# RF_Switch.net
KiCad netlist of a schematic drawn in Altium Designer
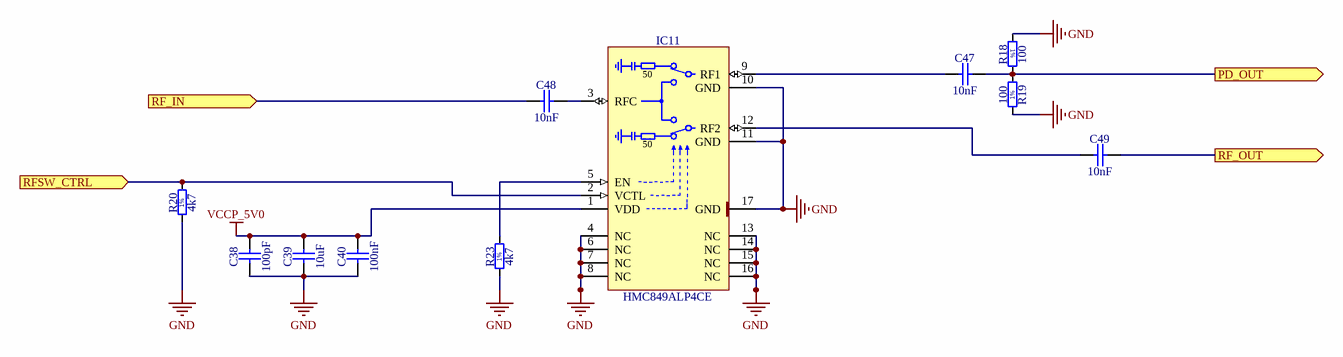
[diagram p0: RF_Switch.SchDoc]

(export (version "E")
  (design (tool "Eeschema 10.0.6"))
  (components
    (comp (ref "C38")
      (value "100pF")
      (footprint "CAPC1005X55N")
      (description "Non-polarised capacitor")
      (fields
        (field (name "PART NUMBER") "CC0402_100PF_50V_5%_C0G")
        (field (name "VOLTAGE") "50V")
        (field (name "AUTHOR") "CERN DEM JLC")
      )
      (libsource (lib "Capacitors") (part "Capacitor - non polarized"))
    )
    (comp (ref "C39")
      (value "10uF")
      (footprint "CAPC1608X80N")
      (description "Non-polarised capacitor")
      (fields
        (field (name "PART NUMBER") "CC0603_10UF_16V_20%_X5R")
        (field (name "VOLTAGE") "16V")
        (field (name "AUTHOR") "CERN DEM MR")
      )
      (libsource (lib "Capacitors") (part "Capacitor - non polarized"))
    )
    (comp (ref "C40")
      (value "100nF")
      (footprint "CAPC1005X55N")
      (description "Non-polarised capacitor")
      (fields
        (field (name "PART NUMBER") "CC0402_100NF_16V_10%_X7R")
        (field (name "VOLTAGE") "16V")
        (field (name "AUTHOR") "CERN DEM JLC")
      )
      (libsource (lib "Capacitors") (part "Capacitor - non polarized"))
    )
    (comp (ref "C47")
      (value "10nF")
      (footprint "CAPC1005X55N")
      (description "Non-polarised capacitor")
      (fields
        (field (name "PART NUMBER") "CC0402_10NF_16V_10%_X7R")
        (field (name "VOLTAGE") "16V")
        (field (name "AUTHOR") "CERN DEM JLC")
      )
      (libsource (lib "Capacitors") (part "Capacitor - non polarized"))
    )
    (comp (ref "C48")
      (value "10nF")
      (footprint "CAPC1005X55N")
      (description "Non-polarised capacitor")
      (fields
        (field (name "PART NUMBER") "CC0402_10NF_16V_10%_X7R")
        (field (name "VOLTAGE") "16V")
        (field (name "AUTHOR") "CERN DEM JLC")
      )
      (libsource (lib "Capacitors") (part "Capacitor - non polarized"))
    )
    (comp (ref "C49")
      (value "10nF")
      (footprint "CAPC1005X55N")
      (description "Non-polarised capacitor")
      (fields
        (field (name "PART NUMBER") "CC0402_10NF_16V_10%_X7R")
        (field (name "VOLTAGE") "16V")
        (field (name "AUTHOR") "CERN DEM JLC")
      )
      (libsource (lib "Capacitors") (part "Capacitor - non polarized"))
    )
    (comp (ref "IC11")
      (value "HMC849ALP4CE")
      (footprint "QFN65P400X400X100-17N-S255")
      (description "High Isolation SPDT Non-Reflective Switch SMT, DC - 6 GHz")
      (fields (field (name "MANUFACTURER") "ANALOG DEVICES") (field (name "AUTHOR") "CERN DEM MR"))
      (libsource (lib "ICs And Semiconductors") (part "HMC849ALP4CE"))
    )
    (comp (ref "R18")
      (value "100")
      (footprint "RESC0603X28N")
      (description "Resistor - 1%")
      (fields
        (field (name "PART NUMBER") "R0201_100R_1%_0.05W_200PPM")
        (field (name "POWER") "0.05W")
        (field (name "AUTHOR") "CERN DEM JLC")
      )
      (libsource (lib "Resistors") (part "Resistor - 1%"))
    )
    (comp (ref "R19")
      (value "100")
      (footprint "RESC0603X28N")
      (description "Resistor - 1%")
      (fields
        (field (name "PART NUMBER") "R0201_100R_1%_0.05W_200PPM")
        (field (name "POWER") "0.05W")
        (field (name "AUTHOR") "CERN DEM JLC")
      )
      (libsource (lib "Resistors") (part "Resistor - 1%"))
    )
    (comp (ref "R20")
      (value "4k7")
      (footprint "RESC1005X40N")
      (description "Resistor - 1%")
      (fields
        (field (name "PART NUMBER") "R0402_4K7_1%_0.0625W_100PPM")
        (field (name "POWER") "0.0625W")
        (field (name "AUTHOR") "CERN DEM JLC")
      )
      (libsource (lib "Resistors") (part "Resistor - 1%"))
    )
    (comp (ref "R23")
      (value "4k7")
      (footprint "RESC1005X40N")
      (description "Resistor - 1%")
      (fields
        (field (name "PART NUMBER") "R0402_4K7_1%_0.0625W_100PPM")
        (field (name "POWER") "0.0625W")
        (field (name "AUTHOR") "CERN DEM JLC")
      )
      (libsource (lib "Resistors") (part "Resistor - 1%"))
    )
  )
  (nets
    (net (code "1") (name "/PD_OUT") (class "Default")
      (node (ref "C47") (pin "2") (pinfunction "2_2") (pintype "passive"))
      (node (ref "R18") (pin "2") (pinfunction "2_2") (pintype "passive"))
      (node (ref "R19") (pin "2") (pinfunction "2_2") (pintype "passive"))
    )
    (net (code "2") (name "/RFSW_CTRL") (class "Default")
      (node (ref "IC11") (pin "2") (pinfunction "VCTL_2") (pintype "input"))
      (node (ref "R20") (pin "2") (pinfunction "2_2") (pintype "passive"))
    )
    (net (code "3") (name "/RF_IN") (class "Default")
      (node (ref "C48") (pin "1") (pinfunction "1_1") (pintype "passive"))
    )
    (net (code "4") (name "/RF_OUT") (class "Default")
      (node (ref "C49") (pin "2") (pinfunction "2_2") (pintype "passive"))
    )
    (net (code "5") (name "GND") (class "Default")
      (node (ref "C38") (pin "2") (pinfunction "2_2") (pintype "passive"))
      (node (ref "C39") (pin "1") (pinfunction "1_1") (pintype "passive"))
      (node (ref "C40") (pin "1") (pinfunction "1_1") (pintype "passive"))
      (node (ref "IC11") (pin "10") (pinfunction "GND_10") (pintype "power_in"))
      (node (ref "IC11") (pin "11") (pinfunction "GND_11") (pintype "power_in"))
      (node (ref "IC11") (pin "13") (pinfunction "NC_13") (pintype "passive"))
      (node (ref "IC11") (pin "14") (pinfunction "NC_14") (pintype "passive"))
      (node (ref "IC11") (pin "15") (pinfunction "NC_15") (pintype "passive"))
      (node (ref "IC11") (pin "16") (pinfunction "NC_16") (pintype "passive"))
      (node (ref "IC11") (pin "17") (pinfunction "GND_17") (pintype "power_in"))
      (node (ref "IC11") (pin "4") (pinfunction "NC_4") (pintype "passive"))
      (node (ref "IC11") (pin "6") (pinfunction "NC_6") (pintype "passive"))
      (node (ref "IC11") (pin "7") (pinfunction "NC_7") (pintype "passive"))
      (node (ref "IC11") (pin "8") (pinfunction "NC_8") (pintype "passive"))
      (node (ref "R18") (pin "1") (pinfunction "1_1") (pintype "passive"))
      (node (ref "R19") (pin "1") (pinfunction "1_1") (pintype "passive"))
      (node (ref "R20") (pin "1") (pinfunction "1_1") (pintype "passive"))
      (node (ref "R23") (pin "1") (pinfunction "1_1") (pintype "passive"))
    )
    (net (code "6") (name "Net-(IC11-EN)") (class "Default")
      (node (ref "IC11") (pin "5") (pinfunction "EN_5") (pintype "input"))
      (node (ref "R23") (pin "2") (pinfunction "2_2") (pintype "passive"))
    )
    (net (code "7") (name "Net-(IC11-RF1)") (class "Default")
      (node (ref "C47") (pin "1") (pinfunction "1_1") (pintype "passive"))
      (node (ref "IC11") (pin "9") (pinfunction "RF1_9") (pintype "bidirectional"))
    )
    (net (code "8") (name "Net-(IC11-RF2)") (class "Default")
      (node (ref "C49") (pin "1") (pinfunction "1_1") (pintype "passive"))
      (node (ref "IC11") (pin "12") (pinfunction "RF2_12") (pintype "bidirectional"))
    )
    (net (code "9") (name "Net-(IC11-RFC)") (class "Default")
      (node (ref "C48") (pin "2") (pinfunction "2_2") (pintype "passive"))
      (node (ref "IC11") (pin "3") (pinfunction "RFC_3") (pintype "bidirectional"))
    )
    (net (code "10") (name "VCCP_5V0") (class "Default")
      (node (ref "C38") (pin "1") (pinfunction "1_1") (pintype "passive"))
      (node (ref "C39") (pin "2") (pinfunction "2_2") (pintype "passive"))
      (node (ref "C40") (pin "2") (pinfunction "2_2") (pintype "passive"))
      (node (ref "IC11") (pin "1") (pinfunction "VDD_1") (pintype "power_in"))
    )
  )
)
